# 12-Power.net
KiCad netlist of a schematic drawn in Altium Designer
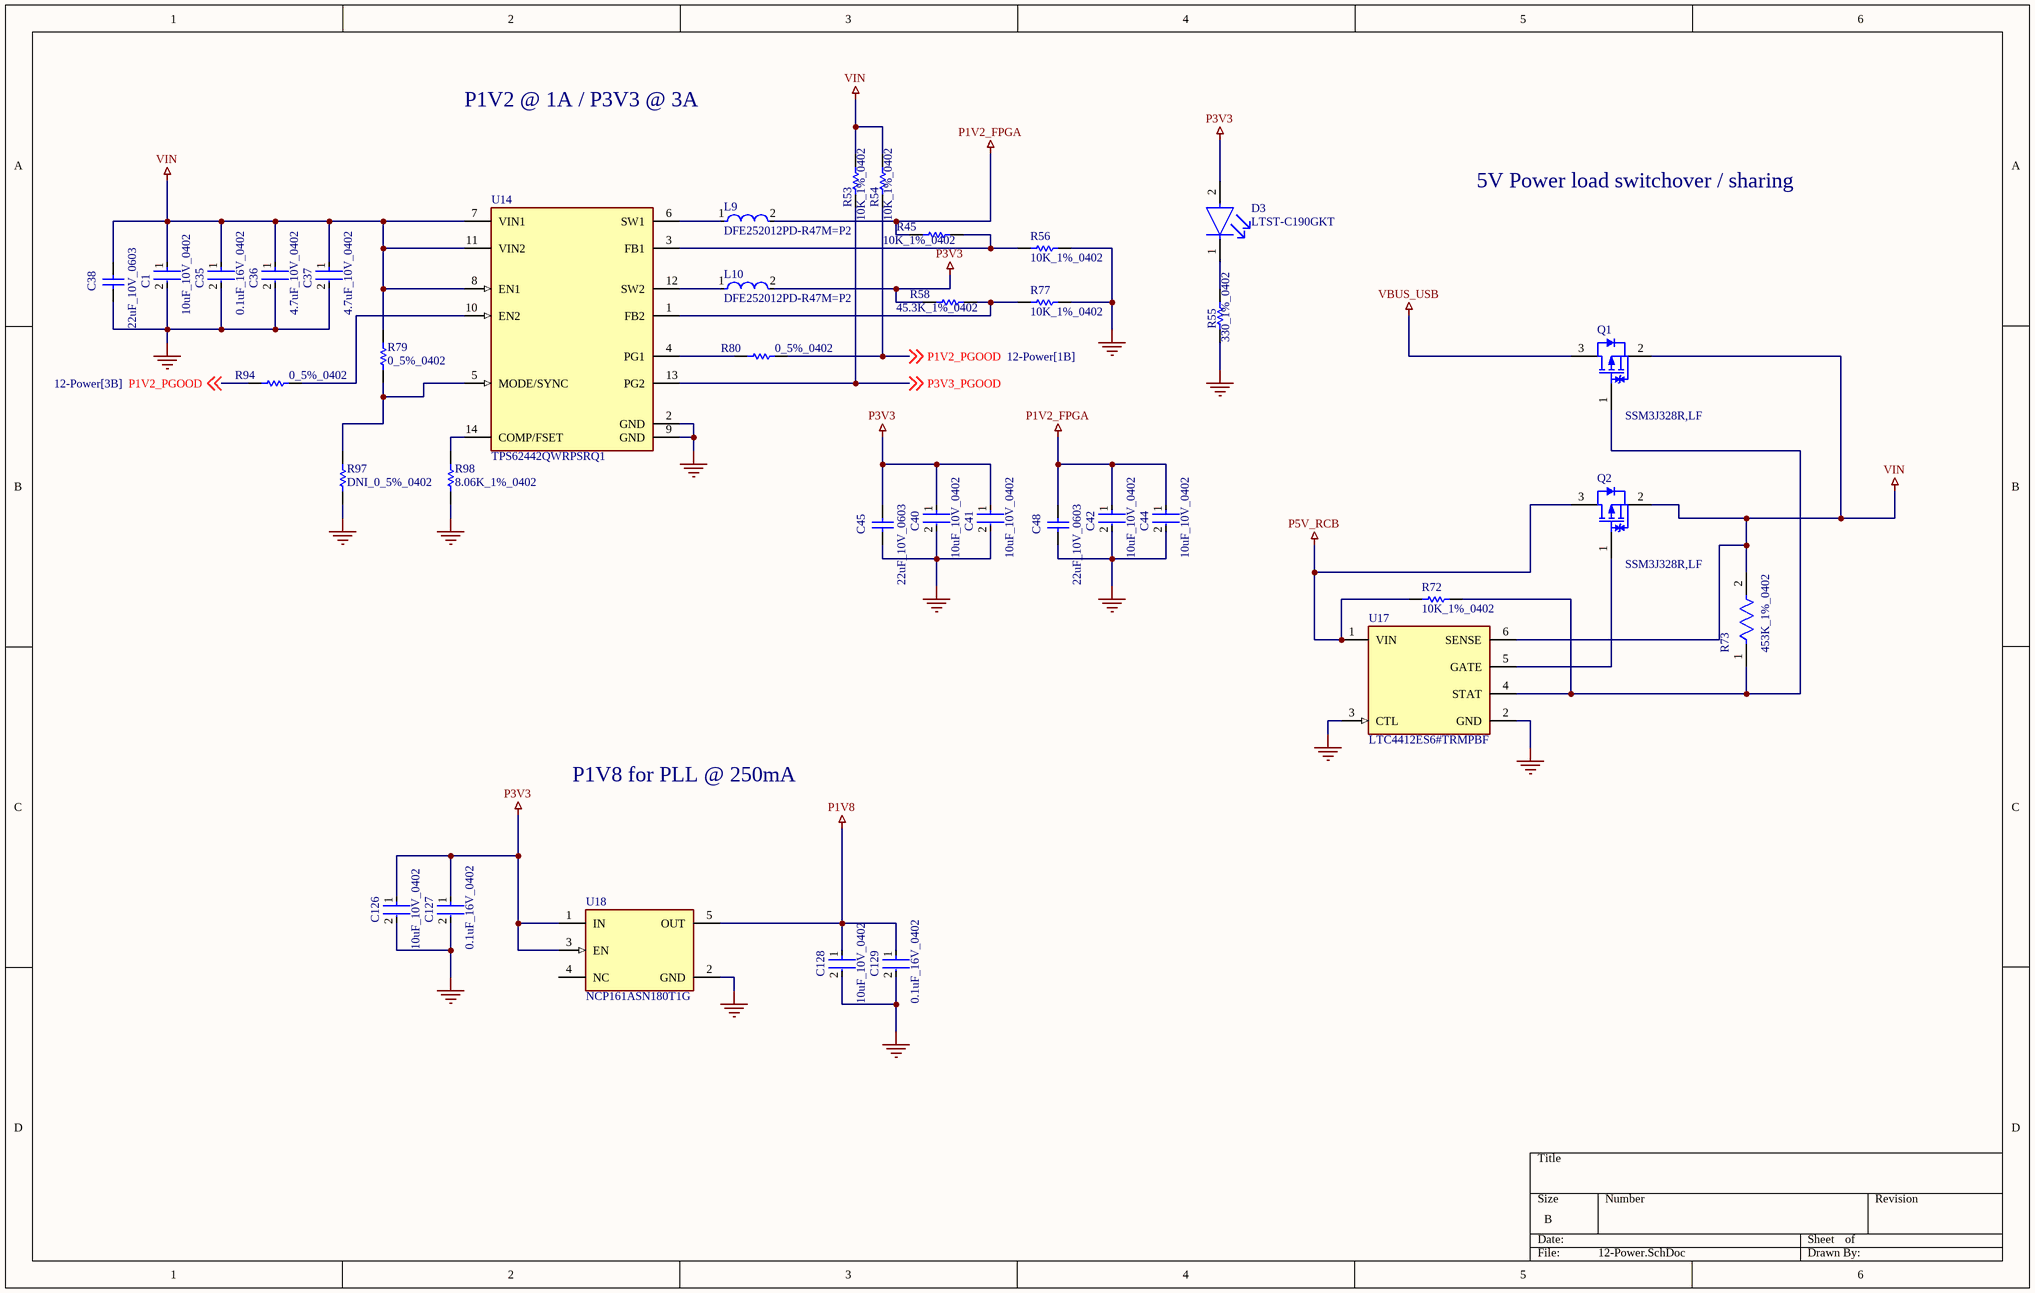
[diagram p0: 12-Power.SchDoc]

(export (version "E")
  (design (tool "Eeschema 10.0.6"))
  (components
    (comp (ref "C1")
      (value "10uF_10V_0402")
      (footprint "FP-CL05A106MP5NUNC-MFG")
      (description "CAP CER 10UF 10V X5R 0402")
      (fields
        (field (name "OCTOPART") "https://octopart.com/cl05a106mp5nunc-samsung-22457395")
        (field (name "TOLERANCE") "20%")
      )
      (libsource (lib "Altium Content Vault") (part "b4654b650e69147ec39a6b967a45e02"))
    )
    (comp (ref "C35")
      (value "0.1uF_16V_0402")
      (footprint "FP-C0402-BB-MFG")
      (description "CAP CER 0.1UF 16V 5% X7R 0402")
      (fields
        (field (name "MANUFACTURER") "Kemet")
        (field (name "MANUFACTURER PART NUMBER") "C0402C104J4RACTU")
      )
      (libsource (lib "Altium Content Vault") (part "b4654b650e69147ec39a6b967a45e02"))
    )
    (comp (ref "C36")
      (value "4.7uF_10V_0402")
      (footprint "FP-C1005-050-0_15-MFG")
      (description "CAP CER 4.7UF 10V X5R 0402")
      (fields (field (name "TOLERANCE") "10%"))
      (libsource (lib "Altium Content Vault") (part "b4654b650e69147ec39a6b967a45e02"))
    )
    (comp (ref "C37")
      (value "4.7uF_10V_0402")
      (footprint "FP-C1005-050-0_15-MFG")
      (description "CAP CER 4.7UF 10V X5R 0402")
      (fields (field (name "TOLERANCE") "10%"))
      (libsource (lib "Altium Content Vault") (part "b4654b650e69147ec39a6b967a45e02"))
    )
    (comp (ref "C38")
      (value "22uF_10V_0603")
      (footprint "CAPC1608X100X20ML10")
      (description "Chip Capacitor, 22 uF, +/- 20%, 10 V, -55 to 85 degC, 0603 (1608 Metric), RoHS, Tape and Reel")
      (fields (field (name "MANUFACTURER") "TDK") (field (name "TOLERANCE") "±20%"))
      (libsource (lib "Altium Content Vault") (part "CAP-NP-2"))
    )
    (comp (ref "C40")
      (value "10uF_10V_0402")
      (footprint "FP-CL05A106MP5NUNC-MFG")
      (description "CAP CER 10UF 10V X5R 0402")
      (fields
        (field (name "OCTOPART") "https://octopart.com/cl05a106mp5nunc-samsung-22457395")
        (field (name "TOLERANCE") "20%")
      )
      (libsource (lib "Altium Content Vault") (part "b4654b650e69147ec39a6b967a45e02"))
    )
    (comp (ref "C41")
      (value "10uF_10V_0402")
      (footprint "FP-CL05A106MP5NUNC-MFG")
      (description "CAP CER 10UF 10V X5R 0402")
      (fields
        (field (name "OCTOPART") "https://octopart.com/cl05a106mp5nunc-samsung-22457395")
        (field (name "TOLERANCE") "20%")
      )
      (libsource (lib "Altium Content Vault") (part "b4654b650e69147ec39a6b967a45e02"))
    )
    (comp (ref "C42")
      (value "10uF_10V_0402")
      (footprint "FP-CL05A106MP5NUNC-MFG")
      (description "CAP CER 10UF 10V X5R 0402")
      (fields
        (field (name "OCTOPART") "https://octopart.com/cl05a106mp5nunc-samsung-22457395")
        (field (name "TOLERANCE") "20%")
      )
      (libsource (lib "Altium Content Vault") (part "b4654b650e69147ec39a6b967a45e02"))
    )
    (comp (ref "C44")
      (value "10uF_10V_0402")
      (footprint "FP-CL05A106MP5NUNC-MFG")
      (description "CAP CER 10UF 10V X5R 0402")
      (fields
        (field (name "OCTOPART") "https://octopart.com/cl05a106mp5nunc-samsung-22457395")
        (field (name "TOLERANCE") "20%")
      )
      (libsource (lib "Altium Content Vault") (part "b4654b650e69147ec39a6b967a45e02"))
    )
    (comp (ref "C45")
      (value "22uF_10V_0603")
      (footprint "CAPC1608X100X20ML10")
      (description "Chip Capacitor, 22 uF, +/- 20%, 10 V, -55 to 85 degC, 0603 (1608 Metric), RoHS, Tape and Reel")
      (fields (field (name "MANUFACTURER") "TDK") (field (name "TOLERANCE") "±20%"))
      (libsource (lib "Altium Content Vault") (part "CAP-NP-2"))
    )
    (comp (ref "C48")
      (value "22uF_10V_0603")
      (footprint "CAPC1608X100X20ML10")
      (description "Chip Capacitor, 22 uF, +/- 20%, 10 V, -55 to 85 degC, 0603 (1608 Metric), RoHS, Tape and Reel")
      (fields (field (name "MANUFACTURER") "TDK") (field (name "TOLERANCE") "±20%"))
      (libsource (lib "Altium Content Vault") (part "CAP-NP-2"))
    )
    (comp (ref "C126")
      (value "10uF_10V_0402")
      (footprint "FP-CL05A106MP5NUNC-MFG")
      (description "CAP CER 10UF 10V X5R 0402")
      (fields
        (field (name "OCTOPART") "https://octopart.com/cl05a106mp5nunc-samsung-22457395")
        (field (name "TOLERANCE") "20%")
      )
      (libsource (lib "Altium Content Vault") (part "b4654b650e69147ec39a6b967a45e02"))
    )
    (comp (ref "C127")
      (value "0.1uF_16V_0402")
      (footprint "FP-C0402-BB-MFG")
      (description "CAP CER 0.1UF 16V 5% X7R 0402")
      (fields
        (field (name "MANUFACTURER") "Kemet")
        (field (name "MANUFACTURER PART NUMBER") "C0402C104J4RACTU")
      )
      (libsource (lib "Altium Content Vault") (part "b4654b650e69147ec39a6b967a45e02"))
    )
    (comp (ref "C128")
      (value "10uF_10V_0402")
      (footprint "FP-CL05A106MP5NUNC-MFG")
      (description "CAP CER 10UF 10V X5R 0402")
      (fields
        (field (name "OCTOPART") "https://octopart.com/cl05a106mp5nunc-samsung-22457395")
        (field (name "TOLERANCE") "20%")
      )
      (libsource (lib "Altium Content Vault") (part "b4654b650e69147ec39a6b967a45e02"))
    )
    (comp (ref "C129")
      (value "0.1uF_16V_0402")
      (footprint "FP-C0402-BB-MFG")
      (description "CAP CER 0.1UF 16V 5% X7R 0402")
      (fields
        (field (name "MANUFACTURER") "Kemet")
        (field (name "MANUFACTURER PART NUMBER") "C0402C104J4RACTU")
      )
      (libsource (lib "Altium Content Vault") (part "b4654b650e69147ec39a6b967a45e02"))
    )
    (comp (ref "D3")
      (value "LTST-C190GKT")
      (footprint "FP-LTST-C190GKT-MFG")
      (description "LED GREEN CLEAR CHIP SMD")
      (fields (field (name "VOLTAGE") "2V"))
      (libsource (lib "Altium Content Vault") (part "8706943c75ba83719d021d2fdc84c58"))
    )
    (comp (ref "L9")
      (value "DFE252012PD-R47M=P2")
      (footprint "FP-DFE252012C-IPC_A")
      (description "Shielded Wirewound Inductor 0.47uH 20% 4000mA 0.027Ω 1008 (2520)")
      (libsource (lib "Altium Content Vault") (part "725321dda6339637d4d059423bc1c3c"))
    )
    (comp (ref "L10")
      (value "DFE252012PD-R47M=P2")
      (footprint "FP-DFE252012C-IPC_A")
      (description "Shielded Wirewound Inductor 0.47uH 20% 4000mA 0.027Ω 1008 (2520)")
      (libsource (lib "Altium Content Vault") (part "725321dda6339637d4d059423bc1c3c"))
    )
    (comp (ref "Q1")
      (value "SSM3J328R,LF")
      (footprint "TOSH-SOT-23F_V")
      (fields (field (name "MANUFACTURER") "Toshiba"))
      (libsource (lib "Altium Content Vault") (part "PEMOS-GSD-3_C"))
    )
    (comp (ref "Q2")
      (value "SSM3J328R,LF")
      (footprint "TOSH-SOT-23F_V")
      (fields (field (name "MANUFACTURER") "Toshiba"))
      (libsource (lib "Altium Content Vault") (part "PEMOS-GSD-3_C"))
    )
    (comp (ref "R45")
      (value "10K_1%_0402")
      (footprint "RESC1005X40X25NL10T10")
      (fields (field (name "MANUFACTURER") "Bourns") (field (name "PART NUMBER") "CR0402-FX-1002GLF"))
      (libsource (lib "Altium Content Vault") (part "RES"))
    )
    (comp (ref "R53")
      (value "10K_1%_0402")
      (footprint "RESC1005X40X25NL10T10")
      (fields (field (name "MANUFACTURER") "Bourns") (field (name "PART NUMBER") "CR0402-FX-1002GLF"))
      (libsource (lib "Altium Content Vault") (part "RES"))
    )
    (comp (ref "R54")
      (value "10K_1%_0402")
      (footprint "RESC1005X40X25NL10T10")
      (fields (field (name "MANUFACTURER") "Bourns") (field (name "PART NUMBER") "CR0402-FX-1002GLF"))
      (libsource (lib "Altium Content Vault") (part "RES"))
    )
    (comp (ref "R55")
      (value "330_1%_0402")
      (footprint "RESC1005X40X25NL10T10")
      (fields (field (name "MANUFACTURER") "Panasonic") (field (name "PART NUMBER") "ERA-2AED331X"))
      (libsource (lib "Altium Content Vault") (part "RES"))
    )
    (comp (ref "R56")
      (value "10K_1%_0402")
      (footprint "RESC1005X40X25NL10T10")
      (fields (field (name "MANUFACTURER") "Bourns") (field (name "PART NUMBER") "CR0402-FX-1002GLF"))
      (libsource (lib "Altium Content Vault") (part "RES"))
    )
    (comp (ref "R58")
      (value "45.3K_1%_0402")
      (footprint "RESC0402(1005)_L")
      (description "45K3 0.063W 1% 0402 (1005 Metric)  SMD")
      (fields (field (name "TOLERANCE") "1 %") (field (name "POWER") "0.063 W"))
      (libsource (lib "Altium Content Vault") (part "RES"))
    )
    (comp (ref "R72")
      (value "10K_1%_0402")
      (footprint "RESC1005X40X25NL10T10")
      (fields (field (name "MANUFACTURER") "Bourns") (field (name "PART NUMBER") "CR0402-FX-1002GLF"))
      (libsource (lib "Altium Content Vault") (part "RES"))
    )
    (comp (ref "R73")
      (value "453K_1%_0402")
      (footprint "FP-RC1005-IPC_B")
      (description "Res Thick Film 0402 453kΩ 1% 0.063W ±100ppm/°C Molded SMD T/R")
      (fields (field (name "TOLERANCE") "1%"))
      (libsource (lib "Altium Content Vault") (part "1029c3af85768c4190bb7ad29bc67b5"))
    )
    (comp (ref "R77")
      (value "10K_1%_0402")
      (footprint "RESC1005X40X25NL10T10")
      (fields (field (name "MANUFACTURER") "Bourns") (field (name "PART NUMBER") "CR0402-FX-1002GLF"))
      (libsource (lib "Altium Content Vault") (part "RES"))
    )
    (comp (ref "R79")
      (value "0_5%_0402")
      (footprint "RESC1005X40X25NL05T10")
      (fields (field (name "MANUFACTURER") "Panasonic") (field (name "PART NUMBER") "ERJ-U020R00X"))
      (libsource (lib "Altium Content Vault") (part "RES"))
    )
    (comp (ref "R80")
      (value "0_5%_0402")
      (footprint "RESC1005X40X25NL05T10")
      (fields (field (name "MANUFACTURER") "Panasonic") (field (name "PART NUMBER") "ERJ-U020R00X"))
      (libsource (lib "Altium Content Vault") (part "RES"))
    )
    (comp (ref "R94")
      (value "0_5%_0402")
      (footprint "RESC1005X40X25NL05T10")
      (fields (field (name "MANUFACTURER") "Panasonic") (field (name "PART NUMBER") "ERJ-U020R00X"))
      (libsource (lib "Altium Content Vault") (part "RES"))
    )
    (comp (ref "R97")
      (value "DNI_0_5%_0402")
      (footprint "RESC1005X40X25NL05T10")
      (fields (field (name "MANUFACTURER") "Panasonic") (field (name "PART NUMBER") "ERJ-U020R00X"))
      (libsource (lib "Altium Content Vault") (part "RES"))
    )
    (comp (ref "R98")
      (value "8.06K_1%_0402")
      (footprint "RESC1005X40X25ML05T05")
      (description "Chip Resistor, 8.06 KOhm, +/- 1%, 63 mW, -55 to 155 degC, 0402 (1005 Metric), RoHS, Tape and Reel")
      (fields (field (name "PARTNUMBER") "CRCW04028K06FKED") (field (name "TOLERANCE") "1%"))
      (libsource (lib "Altium Content Vault") (part "RES-2"))
    )
    (comp (ref "U14")
      (value "TPS62442QWRPSRQ1")
      (footprint "FP-RQR0014A-MFG")
      (description "Adjustable-Frequency Dual Step-Down Converter, 2.7-6V VIN, 0.6-5.5V 2A VOUT, VQFN-HR14")
      (libsource (lib "Altium Content Vault") (part "72c5b9bb22caeb688b1070b758806aa"))
    )
    (comp (ref "U17")
      (value "LTC4412ES6#TRMPBF")
      (footprint "FP-S6-6-05-08-1636-IPC_C")
      (description "IC OR CTRLR SRC SELECT TSOT23-6")
      (libsource (lib "Altium Content Vault") (part "07cb0f4431a3a7488227ca1baae77bb"))
    )
    (comp (ref "U18")
      (value "NCP161ASN180T1G")
      (footprint "FP-527AH-MFG")
      (libsource (lib "Altium Content Vault") (part "07e51adf658dd7550fcbd1980b41b01"))
    )
  )
  (nets
    (net (code "1") (name "GND") (class "Default")
      (node (ref "C1") (pin "2") (pinfunction "2_2") (pintype "passive"))
      (node (ref "C126") (pin "2") (pinfunction "2_2") (pintype "passive"))
      (node (ref "C127") (pin "2") (pinfunction "2_2") (pintype "passive"))
      (node (ref "C128") (pin "2") (pinfunction "2_2") (pintype "passive"))
      (node (ref "C129") (pin "2") (pinfunction "2_2") (pintype "passive"))
      (node (ref "C35") (pin "2") (pinfunction "2_2") (pintype "passive"))
      (node (ref "C36") (pin "2") (pinfunction "2_2") (pintype "passive"))
      (node (ref "C37") (pin "2") (pinfunction "2_2") (pintype "passive"))
      (node (ref "C38") (pin "1") (pinfunction "1_1") (pintype "passive"))
      (node (ref "C40") (pin "2") (pinfunction "2_2") (pintype "passive"))
      (node (ref "C41") (pin "2") (pinfunction "2_2") (pintype "passive"))
      (node (ref "C42") (pin "2") (pinfunction "2_2") (pintype "passive"))
      (node (ref "C44") (pin "2") (pinfunction "2_2") (pintype "passive"))
      (node (ref "C45") (pin "1") (pinfunction "1_1") (pintype "passive"))
      (node (ref "C48") (pin "1") (pinfunction "1_1") (pintype "passive"))
      (node (ref "R55") (pin "1") (pinfunction "1_1") (pintype "passive"))
      (node (ref "R56") (pin "1") (pinfunction "1_1") (pintype "passive"))
      (node (ref "R77") (pin "1") (pinfunction "1_1") (pintype "passive"))
      (node (ref "R97") (pin "1") (pinfunction "1_1") (pintype "passive"))
      (node (ref "R98") (pin "1") (pinfunction "1_1") (pintype "passive"))
      (node (ref "U14") (pin "2") (pinfunction "GND_2") (pintype "power_in"))
      (node (ref "U14") (pin "9") (pinfunction "GND_9") (pintype "power_in"))
      (node (ref "U17") (pin "2") (pinfunction "GND_2") (pintype "power_in"))
      (node (ref "U17") (pin "3") (pinfunction "CTL_3") (pintype "input"))
      (node (ref "U18") (pin "2") (pinfunction "GND_2") (pintype "power_in"))
    )
    (net (code "2") (name "Net-(D3-C)") (class "Default")
      (node (ref "D3") (pin "1") (pinfunction "C_1") (pintype "passive"))
      (node (ref "R55") (pin "2") (pinfunction "2_2") (pintype "passive"))
    )
    (net (code "3") (name "Net-(Q1-G)") (class "Default")
      (node (ref "Q1") (pin "1") (pinfunction "G_1") (pintype "passive"))
      (node (ref "R72") (pin "2") (pinfunction "2_2") (pintype "passive"))
      (node (ref "R73") (pin "1") (pinfunction "1_1") (pintype "passive"))
      (node (ref "U17") (pin "4") (pinfunction "STAT_4") (pintype "open_collector"))
    )
    (net (code "4") (name "Net-(Q2-G)") (class "Default")
      (node (ref "Q2") (pin "1") (pinfunction "G_1") (pintype "passive"))
      (node (ref "U17") (pin "5") (pinfunction "GATE_5") (pintype "passive"))
    )
    (net (code "5") (name "Net-(U14-COMP{slash}FSET)") (class "Default")
      (node (ref "R98") (pin "2") (pinfunction "2_2") (pintype "passive"))
      (node (ref "U14") (pin "14") (pinfunction "COMP/FSET_14") (pintype "passive"))
    )
    (net (code "6") (name "Net-(U14-EN2)") (class "Default")
      (node (ref "R94") (pin "2") (pinfunction "2_2") (pintype "passive"))
      (node (ref "U14") (pin "10") (pinfunction "EN2_10") (pintype "input"))
    )
    (net (code "7") (name "Net-(U14-FB1)") (class "Default")
      (node (ref "R45") (pin "1") (pinfunction "1_1") (pintype "passive"))
      (node (ref "R56") (pin "2") (pinfunction "2_2") (pintype "passive"))
      (node (ref "U14") (pin "3") (pinfunction "FB1_3") (pintype "passive"))
    )
    (net (code "8") (name "Net-(U14-FB2)") (class "Default")
      (node (ref "R58") (pin "2") (pinfunction "2_2") (pintype "passive"))
      (node (ref "R77") (pin "2") (pinfunction "2_2") (pintype "passive"))
      (node (ref "U14") (pin "1") (pinfunction "FB2_1") (pintype "passive"))
    )
    (net (code "9") (name "Net-(U14-MODE{slash}SYNC)") (class "Default")
      (node (ref "R79") (pin "1") (pinfunction "1_1") (pintype "passive"))
      (node (ref "R97") (pin "2") (pinfunction "2_2") (pintype "passive"))
      (node (ref "U14") (pin "5") (pinfunction "MODE/SYNC_5") (pintype "input"))
    )
    (net (code "10") (name "Net-(U14-PG1)") (class "Default")
      (node (ref "R80") (pin "1") (pinfunction "1_1") (pintype "passive"))
      (node (ref "U14") (pin "4") (pinfunction "PG1_4") (pintype "open_collector"))
    )
    (net (code "11") (name "Net-(U14-SW1)") (class "Default")
      (node (ref "L9") (pin "1") (pinfunction "1_1") (pintype "passive"))
      (node (ref "U14") (pin "6") (pinfunction "SW1_6") (pintype "passive"))
    )
    (net (code "12") (name "Net-(U14-SW2)") (class "Default")
      (node (ref "L10") (pin "1") (pinfunction "1_1") (pintype "passive"))
      (node (ref "U14") (pin "12") (pinfunction "SW2_12") (pintype "passive"))
    )
    (net (code "13") (name "P1V2_FPGA") (class "Default")
      (node (ref "C42") (pin "1") (pinfunction "1_1") (pintype "passive"))
      (node (ref "C44") (pin "1") (pinfunction "1_1") (pintype "passive"))
      (node (ref "C48") (pin "2") (pinfunction "2_2") (pintype "passive"))
      (node (ref "L9") (pin "2") (pinfunction "2_2") (pintype "passive"))
      (node (ref "R45") (pin "2") (pinfunction "2_2") (pintype "passive"))
    )
    (net (code "14") (name "P1V2_PGOOD") (class "Default")
      (node (ref "R54") (pin "1") (pinfunction "1_1") (pintype "passive"))
      (node (ref "R80") (pin "2") (pinfunction "2_2") (pintype "passive"))
      (node (ref "R94") (pin "1") (pinfunction "1_1") (pintype "passive"))
    )
    (net (code "15") (name "P1V8") (class "Default")
      (node (ref "C128") (pin "1") (pinfunction "1_1") (pintype "passive"))
      (node (ref "C129") (pin "1") (pinfunction "1_1") (pintype "passive"))
      (node (ref "U18") (pin "5") (pinfunction "OUT_5") (pintype "passive"))
    )
    (net (code "16") (name "P3V3") (class "Default")
      (node (ref "C126") (pin "1") (pinfunction "1_1") (pintype "passive"))
      (node (ref "C127") (pin "1") (pinfunction "1_1") (pintype "passive"))
      (node (ref "C40") (pin "1") (pinfunction "1_1") (pintype "passive"))
      (node (ref "C41") (pin "1") (pinfunction "1_1") (pintype "passive"))
      (node (ref "C45") (pin "2") (pinfunction "2_2") (pintype "passive"))
      (node (ref "D3") (pin "2") (pinfunction "A_2") (pintype "passive"))
      (node (ref "L10") (pin "2") (pinfunction "2_2") (pintype "passive"))
      (node (ref "R58") (pin "1") (pinfunction "1_1") (pintype "passive"))
      (node (ref "U18") (pin "1") (pinfunction "IN_1") (pintype "power_in"))
      (node (ref "U18") (pin "3") (pinfunction "EN_3") (pintype "input"))
    )
    (net (code "17") (name "P3V3_PGOOD") (class "Default")
      (node (ref "R53") (pin "1") (pinfunction "1_1") (pintype "passive"))
      (node (ref "U14") (pin "13") (pinfunction "PG2_13") (pintype "open_collector"))
    )
    (net (code "18") (name "P5V_RCB") (class "Default")
      (node (ref "Q2") (pin "3") (pinfunction "D_3") (pintype "passive"))
      (node (ref "R72") (pin "1") (pinfunction "1_1") (pintype "passive"))
      (node (ref "U17") (pin "1") (pinfunction "VIN_1") (pintype "power_in"))
    )
    (net (code "19") (name "VBUS_USB") (class "Default")
      (node (ref "Q1") (pin "3") (pinfunction "D_3") (pintype "passive"))
    )
    (net (code "20") (name "VIN") (class "Default")
      (node (ref "C1") (pin "1") (pinfunction "1_1") (pintype "passive"))
      (node (ref "C35") (pin "1") (pinfunction "1_1") (pintype "passive"))
      (node (ref "C36") (pin "1") (pinfunction "1_1") (pintype "passive"))
      (node (ref "C37") (pin "1") (pinfunction "1_1") (pintype "passive"))
      (node (ref "C38") (pin "2") (pinfunction "2_2") (pintype "passive"))
      (node (ref "Q1") (pin "2") (pinfunction "S_2") (pintype "passive"))
      (node (ref "Q2") (pin "2") (pinfunction "S_2") (pintype "passive"))
      (node (ref "R53") (pin "2") (pinfunction "2_2") (pintype "passive"))
      (node (ref "R54") (pin "2") (pinfunction "2_2") (pintype "passive"))
      (node (ref "R73") (pin "2") (pinfunction "2_2") (pintype "passive"))
      (node (ref "R79") (pin "2") (pinfunction "2_2") (pintype "passive"))
      (node (ref "U14") (pin "11") (pinfunction "VIN2_11") (pintype "power_in"))
      (node (ref "U14") (pin "7") (pinfunction "VIN1_7") (pintype "power_in"))
      (node (ref "U14") (pin "8") (pinfunction "EN1_8") (pintype "input"))
      (node (ref "U17") (pin "6") (pinfunction "SENSE_6") (pintype "passive"))
    )
    (net (code "21") (name "unconnected-(U18-NC-Pad4)") (class "Default")
      (node (ref "U18") (pin "4") (pinfunction "NC_4") (pintype "passive"))
    )
  )
)
